# Power_Distribution_Unit.net
KiCad netlist of a schematic drawn in Altium Designer
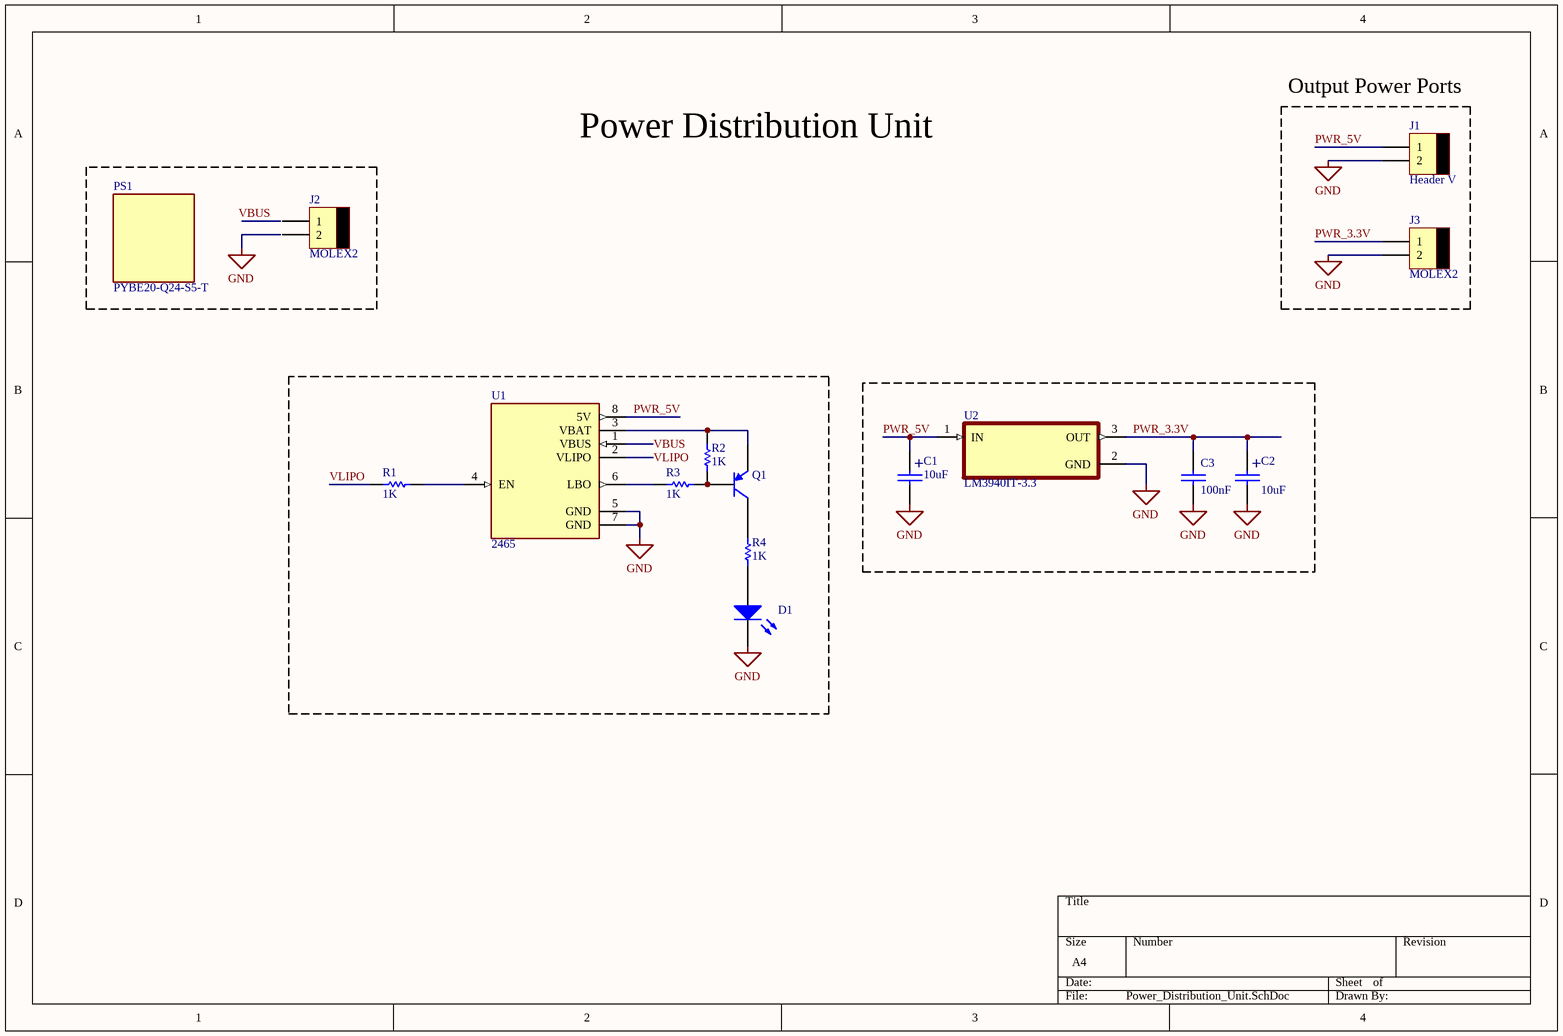
[diagram p0: Power_Distribution_Unit.SchDoc]

(export (version "E")
  (design (tool "Eeschema 10.0.6"))
  (components
    (comp (ref "C1") (value "10uF") (footprint "CAP100RP") (libsource (lib "LIBEBAL") (part "CAPPOL")))
    (comp (ref "C2") (value "10uF") (footprint "CAP100RP") (libsource (lib "LIBEBAL") (part "CAPPOL")))
    (comp (ref "C3") (value "100nF") (footprint "CAP200") (libsource (lib "LIBEBAL") (part "CAP")))
    (comp (ref "D1")
      (value "Light-Emitting Diode")
      (libsource (lib "Simulation Generic Components") (part "LED"))
    )
    (comp (ref "J1") (value "Header V") (footprint "MOLEX2") (libsource (lib "LIBEBAL") (part "MOLEX2")))
    (comp (ref "J2") (value "MOLEX2") (footprint "MOLEX2") (libsource (lib "LIBEBAL") (part "MOLEX2")))
    (comp (ref "J3") (value "MOLEX2") (footprint "MOLEX2") (libsource (lib "LIBEBAL") (part "MOLEX2")))
    (comp (ref "PS1")
      (value "PYBE20-Q24-S5-T")
      (footprint "PYBE20-Q24-S5-T")
      (description "DC-DC Converters")
      (libsource (lib "SiProFaSi") (part "PYBE20-Q24-S5-T"))
    )
    (comp (ref "Q1")
      (value "Bipolar PNP 3 Pins Transistor Gummel-Poon Model")
      (libsource (lib "Simulation Generic Components") (part "BJT PNP GP"))
    )
    (comp (ref "R1")
      (value "1K")
      (description "Resistor")
      (libsource (lib "Simulation Generic Components") (part "Resistor"))
    )
    (comp (ref "R2")
      (value "1K")
      (description "Resistor")
      (libsource (lib "Simulation Generic Components") (part "Resistor"))
    )
    (comp (ref "R3")
      (value "1K")
      (description "Resistor")
      (libsource (lib "Simulation Generic Components") (part "Resistor"))
    )
    (comp (ref "R4")
      (value "1K")
      (description "Resistor")
      (libsource (lib "Simulation Generic Components") (part "Resistor"))
    )
    (comp (ref "U1")
      (value "2465")
      (footprint "MODULE_2465")
      (description "PowerBoost 1000 Charger - Rechargeable 5V Lipo USB Boost at 1A - 1000C")
      (fields (field (name "MF") "Adafruit Industries"))
      (libsource (lib "TD") (part "2465"))
    )
    (comp (ref "U2")
      (value "LM3940IT-3.3")
      (footprint "TO254P1054X470X1955-3")
      (description "1A Low Dropout Regulator for 5V to 3.3V Conversion")
      (fields (field (name "MF") "Texas Instruments") (field (name "MP") "LM3940IT-3.3/NOPB"))
      (libsource (lib "TD") (part "LM3940IT-3.3"))
    )
  )
  (nets
    (net (code "1") (name "/PWR_3.3V") (class "Default")
      (node (ref "C2") (pin "1") (pinfunction "1_1") (pintype "passive"))
      (node (ref "C3") (pin "1") (pinfunction "1_1") (pintype "passive"))
      (node (ref "J3") (pin "1") (pinfunction "1_1") (pintype "passive"))
      (node (ref "U2") (pin "3") (pinfunction "OUT_3") (pintype "output"))
    )
    (net (code "2") (name "/PWR_5V") (class "Default")
      (node (ref "C1") (pin "1") (pinfunction "1_1") (pintype "passive"))
      (node (ref "J1") (pin "1") (pinfunction "1_1") (pintype "passive"))
      (node (ref "U1") (pin "8") (pinfunction "5V_8") (pintype "output"))
      (node (ref "U2") (pin "1") (pinfunction "IN_1") (pintype "input"))
    )
    (net (code "3") (name "/VBUS") (class "Default")
      (node (ref "U1") (pin "1") (pinfunction "VBUS_1") (pintype "input"))
    )
    (net (code "4") (name "/VLIPO") (class "Default")
      (node (ref "R1") (pin "2") (pinfunction "2_2") (pintype "passive"))
      (node (ref "U1") (pin "2") (pinfunction "VLIPO_2") (pintype "passive"))
    )
    (net (code "5") (name "GND") (class "Default")
      (node (ref "C1") (pin "2") (pinfunction "2_2") (pintype "passive"))
      (node (ref "C2") (pin "2") (pinfunction "2_2") (pintype "passive"))
      (node (ref "C3") (pin "2") (pinfunction "2_2") (pintype "passive"))
      (node (ref "D1") (pin "2") (pinfunction "K_2") (pintype "passive"))
      (node (ref "J1") (pin "2") (pinfunction "2_2") (pintype "passive"))
      (node (ref "J3") (pin "2") (pinfunction "2_2") (pintype "passive"))
      (node (ref "U1") (pin "5") (pinfunction "GND_5") (pintype "passive"))
      (node (ref "U1") (pin "7") (pinfunction "GND_7") (pintype "passive"))
      (node (ref "U2") (pin "2") (pinfunction "GND_2") (pintype "passive"))
    )
    (net (code "6") (name "Net-(D1-A)") (class "Default")
      (node (ref "D1") (pin "1") (pinfunction "A_1") (pintype "passive"))
      (node (ref "R4") (pin "1") (pinfunction "1_1") (pintype "passive"))
    )
    (net (code "7") (name "Net-(Q1-B)") (class "Default")
      (node (ref "Q1") (pin "2") (pinfunction "B_2") (pintype "passive"))
      (node (ref "R2") (pin "1") (pinfunction "1_1") (pintype "passive"))
      (node (ref "R3") (pin "1") (pinfunction "1_1") (pintype "passive"))
    )
    (net (code "8") (name "Net-(Q1-C)") (class "Default")
      (node (ref "Q1") (pin "1") (pinfunction "C_1") (pintype "passive"))
      (node (ref "R4") (pin "2") (pinfunction "2_2") (pintype "passive"))
    )
    (net (code "9") (name "Net-(Q1-E)") (class "Default")
      (node (ref "Q1") (pin "3") (pinfunction "E_3") (pintype "passive"))
      (node (ref "R2") (pin "2") (pinfunction "2_2") (pintype "passive"))
      (node (ref "U1") (pin "3") (pinfunction "VBAT_3") (pintype "power_in"))
    )
    (net (code "10") (name "Net-(U1-EN)") (class "Default")
      (node (ref "R1") (pin "1") (pinfunction "1_1") (pintype "passive"))
      (node (ref "U1") (pin "4") (pinfunction "EN_4") (pintype "input"))
    )
    (net (code "11") (name "Net-(U1-LBO)") (class "Default")
      (node (ref "R3") (pin "2") (pinfunction "2_2") (pintype "passive"))
      (node (ref "U1") (pin "6") (pinfunction "LBO_6") (pintype "output"))
    )
    (net (code "12") (name "unconnected-(J2-Pad1)") (class "Default")
      (node (ref "J2") (pin "1") (pinfunction "1_1") (pintype "passive"))
    )
    (net (code "13") (name "unconnected-(J2-Pad2)") (class "Default")
      (node (ref "J2") (pin "2") (pinfunction "2_2") (pintype "passive"))
    )
  )
)
